# SH5_-_NETZER_ENCODERS.net
KiCad netlist of a schematic drawn in Altium Designer
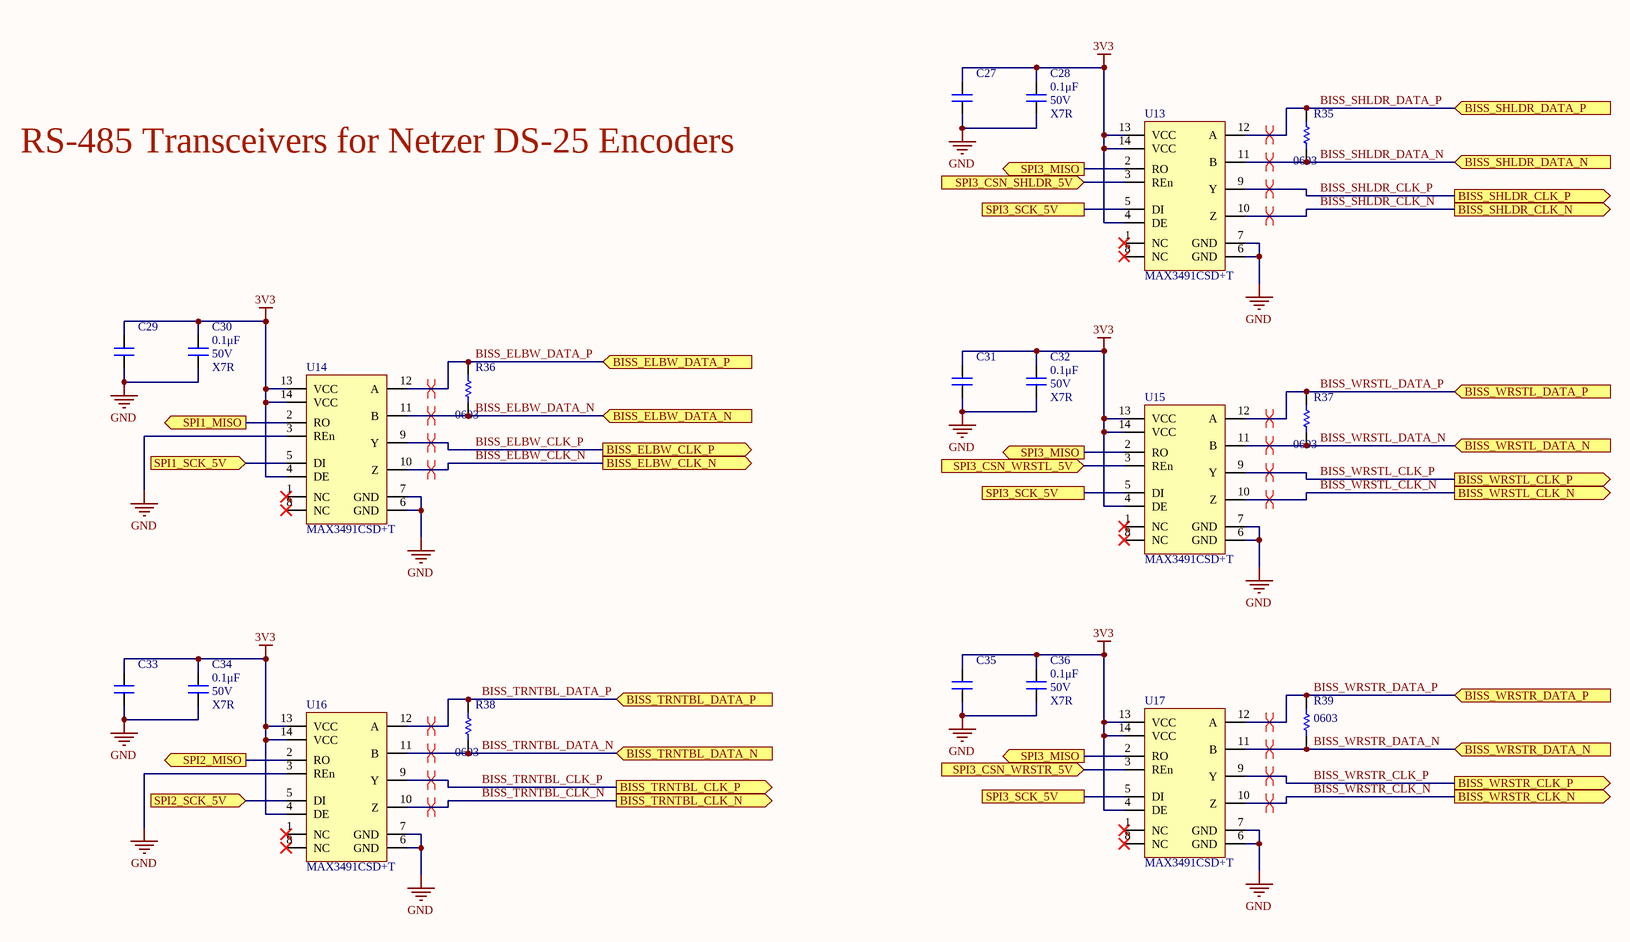
[diagram p0: SH5 - NETZER ENCODERS.SchDoc]

(export (version "E")
  (design (tool "Eeschema 10.0.6"))
  (components
    (comp (ref "C27")
      (value "CAP_1uF_25V_0603")
      (footprint "CAP0603")
      (description "CAP CER 1UF 25V X5R 0603")
      (libsource (lib "UWRT_Schematic_Library_2020") (part "CAP_1uF_25V_0603"))
    )
    (comp (ref "C28")
      (value "0.1μF")
      (footprint "CAP0603")
      (description "CAP CER 0.1UF 50V X7R 0603")
      (fields
        (field (name "DIELECTRIC") "X7R")
        (field (name "VOLTAGE RATING") "50V")
        (field (name "Comment") "CAP_0.1uF_50V_0603")
      )
      (libsource (lib "UWRT_Schematic_Library_2020") (part "CAP_0.1uF_50V_0603"))
    )
    (comp (ref "C29")
      (value "CAP_1uF_25V_0603")
      (footprint "CAP0603")
      (description "CAP CER 1UF 25V X5R 0603")
      (libsource (lib "UWRT_Schematic_Library_2020") (part "CAP_1uF_25V_0603"))
    )
    (comp (ref "C30")
      (value "0.1μF")
      (footprint "CAP0603")
      (description "CAP CER 0.1UF 50V X7R 0603")
      (fields
        (field (name "DIELECTRIC") "X7R")
        (field (name "VOLTAGE RATING") "50V")
        (field (name "Comment") "CAP_0.1uF_50V_0603")
      )
      (libsource (lib "UWRT_Schematic_Library_2020") (part "CAP_0.1uF_50V_0603"))
    )
    (comp (ref "C31")
      (value "CAP_1uF_25V_0603")
      (footprint "CAP0603")
      (description "CAP CER 1UF 25V X5R 0603")
      (libsource (lib "UWRT_Schematic_Library_2020") (part "CAP_1uF_25V_0603"))
    )
    (comp (ref "C32")
      (value "0.1μF")
      (footprint "CAP0603")
      (description "CAP CER 0.1UF 50V X7R 0603")
      (fields
        (field (name "DIELECTRIC") "X7R")
        (field (name "VOLTAGE RATING") "50V")
        (field (name "Comment") "CAP_0.1uF_50V_0603")
      )
      (libsource (lib "UWRT_Schematic_Library_2020") (part "CAP_0.1uF_50V_0603"))
    )
    (comp (ref "C33")
      (value "CAP_1uF_25V_0603")
      (footprint "CAP0603")
      (description "CAP CER 1UF 25V X5R 0603")
      (libsource (lib "UWRT_Schematic_Library_2020") (part "CAP_1uF_25V_0603"))
    )
    (comp (ref "C34")
      (value "0.1μF")
      (footprint "CAP0603")
      (description "CAP CER 0.1UF 50V X7R 0603")
      (fields
        (field (name "DIELECTRIC") "X7R")
        (field (name "VOLTAGE RATING") "50V")
        (field (name "Comment") "CAP_0.1uF_50V_0603")
      )
      (libsource (lib "UWRT_Schematic_Library_2020") (part "CAP_0.1uF_50V_0603"))
    )
    (comp (ref "C35")
      (value "CAP_1uF_25V_0603")
      (footprint "CAP0603")
      (description "CAP CER 1UF 25V X5R 0603")
      (libsource (lib "UWRT_Schematic_Library_2020") (part "CAP_1uF_25V_0603"))
    )
    (comp (ref "C36")
      (value "0.1μF")
      (footprint "CAP0603")
      (description "CAP CER 0.1UF 50V X7R 0603")
      (fields
        (field (name "DIELECTRIC") "X7R")
        (field (name "VOLTAGE RATING") "50V")
        (field (name "Comment") "CAP_0.1uF_50V_0603")
      )
      (libsource (lib "UWRT_Schematic_Library_2020") (part "CAP_0.1uF_50V_0603"))
    )
    (comp (ref "R35")
      (value "RES_120Ω_0603_5%_HP")
      (footprint "RESC0603")
      (description "RES 120 OHM 5% 1/4W 0603")
      (fields (field (name "PACKAGE/FOOTPRINT") "0603"))
      (libsource (lib "UWRT_Schematic_Library_2020") (part "RES_120Ω_0603_5%_HP"))
    )
    (comp (ref "R36")
      (value "RES_120Ω_0603_5%_HP")
      (footprint "RESC0603")
      (description "RES 120 OHM 5% 1/4W 0603")
      (fields (field (name "PACKAGE/FOOTPRINT") "0603"))
      (libsource (lib "UWRT_Schematic_Library_2020") (part "RES_120Ω_0603_5%_HP"))
    )
    (comp (ref "R37")
      (value "RES_120Ω_0603_5%_HP")
      (footprint "RESC0603")
      (description "RES 120 OHM 5% 1/4W 0603")
      (fields (field (name "PACKAGE/FOOTPRINT") "0603"))
      (libsource (lib "UWRT_Schematic_Library_2020") (part "RES_120Ω_0603_5%_HP"))
    )
    (comp (ref "R38")
      (value "RES_120Ω_0603_5%_HP")
      (footprint "RESC0603")
      (description "RES 120 OHM 5% 1/4W 0603")
      (fields (field (name "PACKAGE/FOOTPRINT") "0603"))
      (libsource (lib "UWRT_Schematic_Library_2020") (part "RES_120Ω_0603_5%_HP"))
    )
    (comp (ref "R39")
      (value "RES_120Ω_0603_5%_HP")
      (footprint "RESC0603")
      (description "RES 120 OHM 5% 1/4W 0603")
      (fields (field (name "PACKAGE/FOOTPRINT") "0603"))
      (libsource (lib "UWRT_Schematic_Library_2020") (part "RES_120Ω_0603_5%_HP"))
    )
    (comp (ref "U13")
      (value "MAX3491")
      (footprint "MAX3491CSD+T")
      (description "IC RS485 TRANSCEIVER FULL 1/1 14SOIC")
      (fields (field (name "MANUFACTURER PART NUMBER 1") "MAX3491CSD+T"))
      (libsource (lib "UWRT_Schematic_Library_2020") (part "MAX3491"))
    )
    (comp (ref "U14")
      (value "MAX3491")
      (footprint "MAX3491CSD+T")
      (description "IC RS485 TRANSCEIVER FULL 1/1 14SOIC")
      (fields (field (name "MANUFACTURER PART NUMBER 1") "MAX3491CSD+T"))
      (libsource (lib "UWRT_Schematic_Library_2020") (part "MAX3491"))
    )
    (comp (ref "U15")
      (value "MAX3491")
      (footprint "MAX3491CSD+T")
      (description "IC RS485 TRANSCEIVER FULL 1/1 14SOIC")
      (fields (field (name "MANUFACTURER PART NUMBER 1") "MAX3491CSD+T"))
      (libsource (lib "UWRT_Schematic_Library_2020") (part "MAX3491"))
    )
    (comp (ref "U16")
      (value "MAX3491")
      (footprint "MAX3491CSD+T")
      (description "IC RS485 TRANSCEIVER FULL 1/1 14SOIC")
      (fields (field (name "MANUFACTURER PART NUMBER 1") "MAX3491CSD+T"))
      (libsource (lib "UWRT_Schematic_Library_2020") (part "MAX3491"))
    )
    (comp (ref "U17")
      (value "MAX3491")
      (footprint "MAX3491CSD+T")
      (description "IC RS485 TRANSCEIVER FULL 1/1 14SOIC")
      (fields (field (name "MANUFACTURER PART NUMBER 1") "MAX3491CSD+T"))
      (libsource (lib "UWRT_Schematic_Library_2020") (part "MAX3491"))
    )
  )
  (nets
    (net (code "1") (name "/BISS_ELBW_CLK_N") (class "Default")
      (node (ref "U14") (pin "10") (pinfunction "Z_10") (pintype "passive"))
    )
    (net (code "2") (name "/BISS_ELBW_CLK_P") (class "Default")
      (node (ref "U14") (pin "9") (pinfunction "Y_9") (pintype "passive"))
    )
    (net (code "3") (name "/BISS_ELBW_DATA_N") (class "Default")
      (node (ref "R36") (pin "1") (pinfunction "1_1") (pintype "passive"))
      (node (ref "U14") (pin "11") (pinfunction "B_11") (pintype "passive"))
    )
    (net (code "4") (name "/BISS_ELBW_DATA_P") (class "Default")
      (node (ref "R36") (pin "2") (pinfunction "2_2") (pintype "passive"))
      (node (ref "U14") (pin "12") (pinfunction "A_12") (pintype "passive"))
    )
    (net (code "5") (name "/BISS_SHLDR_CLK_N") (class "Default")
      (node (ref "U13") (pin "10") (pinfunction "Z_10") (pintype "passive"))
    )
    (net (code "6") (name "/BISS_SHLDR_CLK_P") (class "Default")
      (node (ref "U13") (pin "9") (pinfunction "Y_9") (pintype "passive"))
    )
    (net (code "7") (name "/BISS_SHLDR_DATA_N") (class "Default")
      (node (ref "R35") (pin "1") (pinfunction "1_1") (pintype "passive"))
      (node (ref "U13") (pin "11") (pinfunction "B_11") (pintype "passive"))
    )
    (net (code "8") (name "/BISS_SHLDR_DATA_P") (class "Default")
      (node (ref "R35") (pin "2") (pinfunction "2_2") (pintype "passive"))
      (node (ref "U13") (pin "12") (pinfunction "A_12") (pintype "passive"))
    )
    (net (code "9") (name "/BISS_TRNTBL_CLK_N") (class "Default")
      (node (ref "U16") (pin "10") (pinfunction "Z_10") (pintype "passive"))
    )
    (net (code "10") (name "/BISS_TRNTBL_CLK_P") (class "Default")
      (node (ref "U16") (pin "9") (pinfunction "Y_9") (pintype "passive"))
    )
    (net (code "11") (name "/BISS_TRNTBL_DATA_N") (class "Default")
      (node (ref "R38") (pin "1") (pinfunction "1_1") (pintype "passive"))
      (node (ref "U16") (pin "11") (pinfunction "B_11") (pintype "passive"))
    )
    (net (code "12") (name "/BISS_TRNTBL_DATA_P") (class "Default")
      (node (ref "R38") (pin "2") (pinfunction "2_2") (pintype "passive"))
      (node (ref "U16") (pin "12") (pinfunction "A_12") (pintype "passive"))
    )
    (net (code "13") (name "/BISS_WRSTL_CLK_N") (class "Default")
      (node (ref "U15") (pin "10") (pinfunction "Z_10") (pintype "passive"))
    )
    (net (code "14") (name "/BISS_WRSTL_CLK_P") (class "Default")
      (node (ref "U15") (pin "9") (pinfunction "Y_9") (pintype "passive"))
    )
    (net (code "15") (name "/BISS_WRSTL_DATA_N") (class "Default")
      (node (ref "R37") (pin "1") (pinfunction "1_1") (pintype "passive"))
      (node (ref "U15") (pin "11") (pinfunction "B_11") (pintype "passive"))
    )
    (net (code "16") (name "/BISS_WRSTL_DATA_P") (class "Default")
      (node (ref "R37") (pin "2") (pinfunction "2_2") (pintype "passive"))
      (node (ref "U15") (pin "12") (pinfunction "A_12") (pintype "passive"))
    )
    (net (code "17") (name "/BISS_WRSTR_CLK_N") (class "Default")
      (node (ref "U17") (pin "10") (pinfunction "Z_10") (pintype "passive"))
    )
    (net (code "18") (name "/BISS_WRSTR_CLK_P") (class "Default")
      (node (ref "U17") (pin "9") (pinfunction "Y_9") (pintype "passive"))
    )
    (net (code "19") (name "/BISS_WRSTR_DATA_N") (class "Default")
      (node (ref "R39") (pin "1") (pinfunction "1_1") (pintype "passive"))
      (node (ref "U17") (pin "11") (pinfunction "B_11") (pintype "passive"))
    )
    (net (code "20") (name "/BISS_WRSTR_DATA_P") (class "Default")
      (node (ref "R39") (pin "2") (pinfunction "2_2") (pintype "passive"))
      (node (ref "U17") (pin "12") (pinfunction "A_12") (pintype "passive"))
    )
    (net (code "21") (name "/SPI1_MISO") (class "Default")
      (node (ref "U14") (pin "2") (pinfunction "RO_2") (pintype "passive"))
    )
    (net (code "22") (name "/SPI1_SCK_5V") (class "Default")
      (node (ref "U14") (pin "5") (pinfunction "DI_5") (pintype "passive"))
    )
    (net (code "23") (name "/SPI2_MISO") (class "Default")
      (node (ref "U16") (pin "2") (pinfunction "RO_2") (pintype "passive"))
    )
    (net (code "24") (name "/SPI2_SCK_5V") (class "Default")
      (node (ref "U16") (pin "5") (pinfunction "DI_5") (pintype "passive"))
    )
    (net (code "25") (name "/SPI3_CSN_SHLDR_5V") (class "Default")
      (node (ref "U13") (pin "3") (pinfunction "REn_3") (pintype "passive"))
    )
    (net (code "26") (name "/SPI3_CSN_WRSTL_5V") (class "Default")
      (node (ref "U15") (pin "3") (pinfunction "REn_3") (pintype "passive"))
    )
    (net (code "27") (name "/SPI3_CSN_WRSTR_5V") (class "Default")
      (node (ref "U17") (pin "3") (pinfunction "REn_3") (pintype "passive"))
    )
    (net (code "28") (name "/SPI3_MISO") (class "Default")
      (node (ref "U13") (pin "2") (pinfunction "RO_2") (pintype "passive"))
      (node (ref "U15") (pin "2") (pinfunction "RO_2") (pintype "passive"))
      (node (ref "U17") (pin "2") (pinfunction "RO_2") (pintype "passive"))
    )
    (net (code "29") (name "/SPI3_SCK_5V") (class "Default")
      (node (ref "U13") (pin "5") (pinfunction "DI_5") (pintype "passive"))
      (node (ref "U15") (pin "5") (pinfunction "DI_5") (pintype "passive"))
      (node (ref "U17") (pin "5") (pinfunction "DI_5") (pintype "passive"))
    )
    (net (code "30") (name "3V3") (class "Default")
      (node (ref "C27") (pin "2") (pinfunction "2_2") (pintype "passive"))
      (node (ref "C28") (pin "2") (pinfunction "2_2") (pintype "passive"))
      (node (ref "C29") (pin "2") (pinfunction "2_2") (pintype "passive"))
      (node (ref "C30") (pin "2") (pinfunction "2_2") (pintype "passive"))
      (node (ref "C31") (pin "2") (pinfunction "2_2") (pintype "passive"))
      (node (ref "C32") (pin "2") (pinfunction "2_2") (pintype "passive"))
      (node (ref "C33") (pin "2") (pinfunction "2_2") (pintype "passive"))
      (node (ref "C34") (pin "2") (pinfunction "2_2") (pintype "passive"))
      (node (ref "C35") (pin "2") (pinfunction "2_2") (pintype "passive"))
      (node (ref "C36") (pin "2") (pinfunction "2_2") (pintype "passive"))
      (node (ref "U13") (pin "13") (pinfunction "VCC_13") (pintype "passive"))
      (node (ref "U13") (pin "14") (pinfunction "VCC_14") (pintype "passive"))
      (node (ref "U13") (pin "4") (pinfunction "DE_4") (pintype "passive"))
      (node (ref "U14") (pin "13") (pinfunction "VCC_13") (pintype "passive"))
      (node (ref "U14") (pin "14") (pinfunction "VCC_14") (pintype "passive"))
      (node (ref "U14") (pin "4") (pinfunction "DE_4") (pintype "passive"))
      (node (ref "U15") (pin "13") (pinfunction "VCC_13") (pintype "passive"))
      (node (ref "U15") (pin "14") (pinfunction "VCC_14") (pintype "passive"))
      (node (ref "U15") (pin "4") (pinfunction "DE_4") (pintype "passive"))
      (node (ref "U16") (pin "13") (pinfunction "VCC_13") (pintype "passive"))
      (node (ref "U16") (pin "14") (pinfunction "VCC_14") (pintype "passive"))
      (node (ref "U16") (pin "4") (pinfunction "DE_4") (pintype "passive"))
      (node (ref "U17") (pin "13") (pinfunction "VCC_13") (pintype "passive"))
      (node (ref "U17") (pin "14") (pinfunction "VCC_14") (pintype "passive"))
      (node (ref "U17") (pin "4") (pinfunction "DE_4") (pintype "passive"))
    )
    (net (code "31") (name "GND") (class "Default")
      (node (ref "C27") (pin "1") (pinfunction "1_1") (pintype "passive"))
      (node (ref "C28") (pin "1") (pinfunction "1_1") (pintype "passive"))
      (node (ref "C29") (pin "1") (pinfunction "1_1") (pintype "passive"))
      (node (ref "C30") (pin "1") (pinfunction "1_1") (pintype "passive"))
      (node (ref "C31") (pin "1") (pinfunction "1_1") (pintype "passive"))
      (node (ref "C32") (pin "1") (pinfunction "1_1") (pintype "passive"))
      (node (ref "C33") (pin "1") (pinfunction "1_1") (pintype "passive"))
      (node (ref "C34") (pin "1") (pinfunction "1_1") (pintype "passive"))
      (node (ref "C35") (pin "1") (pinfunction "1_1") (pintype "passive"))
      (node (ref "C36") (pin "1") (pinfunction "1_1") (pintype "passive"))
      (node (ref "U13") (pin "6") (pinfunction "GND_6") (pintype "passive"))
      (node (ref "U13") (pin "7") (pinfunction "GND_7") (pintype "passive"))
      (node (ref "U14") (pin "3") (pinfunction "REn_3") (pintype "passive"))
      (node (ref "U14") (pin "6") (pinfunction "GND_6") (pintype "passive"))
      (node (ref "U14") (pin "7") (pinfunction "GND_7") (pintype "passive"))
      (node (ref "U15") (pin "6") (pinfunction "GND_6") (pintype "passive"))
      (node (ref "U15") (pin "7") (pinfunction "GND_7") (pintype "passive"))
      (node (ref "U16") (pin "3") (pinfunction "REn_3") (pintype "passive"))
      (node (ref "U16") (pin "6") (pinfunction "GND_6") (pintype "passive"))
      (node (ref "U16") (pin "7") (pinfunction "GND_7") (pintype "passive"))
      (node (ref "U17") (pin "6") (pinfunction "GND_6") (pintype "passive"))
      (node (ref "U17") (pin "7") (pinfunction "GND_7") (pintype "passive"))
    )
    (net (code "32") (name "unconnected-(U13-NC-Pad1)") (class "Default")
      (node (ref "U13") (pin "1") (pinfunction "NC_1") (pintype "passive+no_connect"))
    )
    (net (code "33") (name "unconnected-(U13-NC-Pad8)") (class "Default")
      (node (ref "U13") (pin "8") (pinfunction "NC_8") (pintype "passive+no_connect"))
    )
    (net (code "34") (name "unconnected-(U14-NC-Pad1)") (class "Default")
      (node (ref "U14") (pin "1") (pinfunction "NC_1") (pintype "passive+no_connect"))
    )
    (net (code "35") (name "unconnected-(U14-NC-Pad8)") (class "Default")
      (node (ref "U14") (pin "8") (pinfunction "NC_8") (pintype "passive+no_connect"))
    )
    (net (code "36") (name "unconnected-(U15-NC-Pad1)") (class "Default")
      (node (ref "U15") (pin "1") (pinfunction "NC_1") (pintype "passive+no_connect"))
    )
    (net (code "37") (name "unconnected-(U15-NC-Pad8)") (class "Default")
      (node (ref "U15") (pin "8") (pinfunction "NC_8") (pintype "passive+no_connect"))
    )
    (net (code "38") (name "unconnected-(U16-NC-Pad1)") (class "Default")
      (node (ref "U16") (pin "1") (pinfunction "NC_1") (pintype "passive+no_connect"))
    )
    (net (code "39") (name "unconnected-(U16-NC-Pad8)") (class "Default")
      (node (ref "U16") (pin "8") (pinfunction "NC_8") (pintype "passive+no_connect"))
    )
    (net (code "40") (name "unconnected-(U17-NC-Pad1)") (class "Default")
      (node (ref "U17") (pin "1") (pinfunction "NC_1") (pintype "passive+no_connect"))
    )
    (net (code "41") (name "unconnected-(U17-NC-Pad8)") (class "Default")
      (node (ref "U17") (pin "8") (pinfunction "NC_8") (pintype "passive+no_connect"))
    )
  )
)
